# RF.net
KiCad netlist of a schematic drawn in Altium Designer
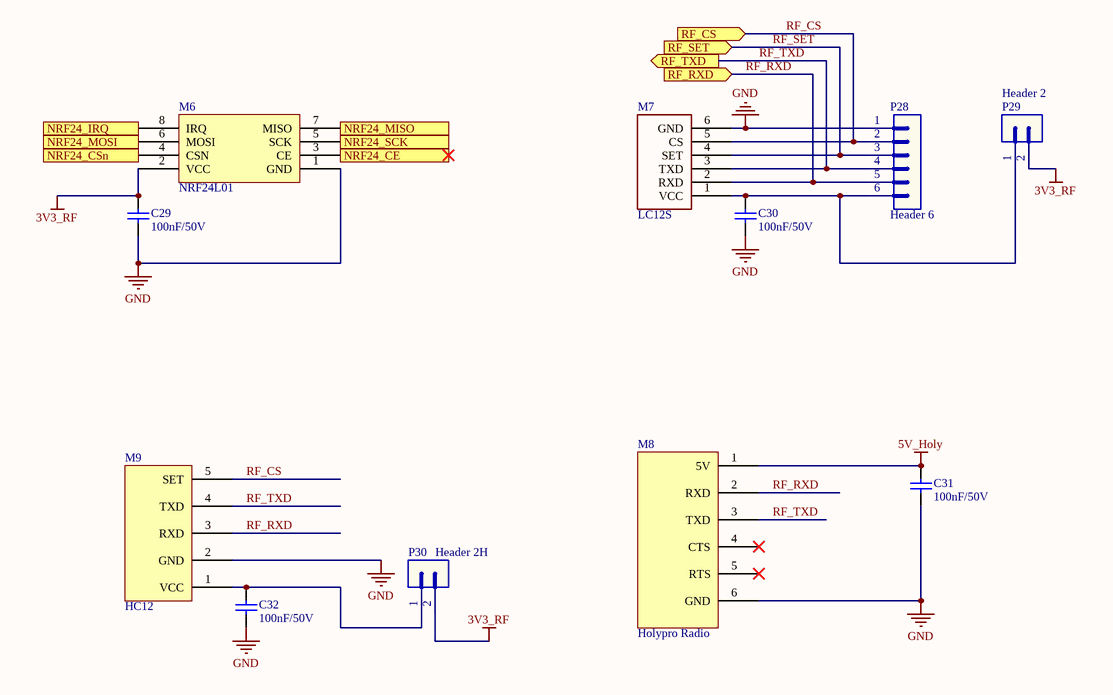
[diagram p0: RF.schdoc]

(export (version "E")
  (design (tool "Eeschema 10.0.6"))
  (components
    (comp (ref "C29")
      (value "100nF/50V")
      (footprint "CAP-SM-0805")
      (description "CAP CER 0.1UF 50V Y5V 0805")
      (fields
        (field (name "MANUFACTURER") "Samsung Electro-Mechanics")
        (field (name "MANUFACTURER PART NUMBER") "CL21F104ZBCNNNC")
      )
      (libsource (lib "Capacitor") (part "Cap-100nF-50V-0805"))
    )
    (comp (ref "C30")
      (value "100nF/50V")
      (footprint "CAP-SM-0805")
      (description "CAP CER 0.1UF 50V Y5V 0805")
      (fields
        (field (name "MANUFACTURER") "Samsung Electro-Mechanics")
        (field (name "MANUFACTURER PART NUMBER") "CL21F104ZBCNNNC")
      )
      (libsource (lib "Capacitor") (part "Cap-100nF-50V-0805"))
    )
    (comp (ref "C31")
      (value "100nF/50V")
      (footprint "CAP-SM-0805")
      (description "CAP CER 0.1UF 50V Y5V 0805")
      (fields
        (field (name "MANUFACTURER") "Samsung Electro-Mechanics")
        (field (name "MANUFACTURER PART NUMBER") "CL21F104ZBCNNNC")
      )
      (libsource (lib "Capacitor") (part "Cap-100nF-50V-0805"))
    )
    (comp (ref "C32")
      (value "100nF/50V")
      (footprint "CAP-SM-0805")
      (description "CAP CER 0.1UF 50V Y5V 0805")
      (fields
        (field (name "MANUFACTURER") "Samsung Electro-Mechanics")
        (field (name "MANUFACTURER PART NUMBER") "CL21F104ZBCNNNC")
      )
      (libsource (lib "Capacitor") (part "Cap-100nF-50V-0805"))
    )
    (comp (ref "M6") (value "NRF24L01") (footprint "NRF24L01") (libsource (lib "Bai1 (1)") (part "NRF24L01")))
    (comp (ref "M7") (value "LC12S") (footprint "LC12S") (libsource (lib "Board") (part "LC12S")))
    (comp (ref "M8")
      (value "Holypro Radio")
      (footprint "holybro:PCBComponent_1")
      (libsource (lib "Bai1 (1)") (part "Holypro Radio"))
    )
    (comp (ref "M9")
      (value "HC12")
      (footprint "hc12 (1):PCBComponent_1")
      (fields (field (name "LOCAL SUPPLIER PART NUMBER") "HS000897"))
      (libsource (lib "Bai1 (1)") (part "HC12"))
    )
    (comp (ref "P28")
      (value "Header 6")
      (footprint "JP6")
      (description "Header, 6-Pin")
      (fields (field (name "PUBLISHER") "Altium Limited"))
      (libsource (lib "Header-connector") (part "Header 6"))
    )
    (comp (ref "P29")
      (value "Header 2")
      (footprint "JP2")
      (description "Header, 2-Pin")
      (fields (field (name "PUBLISHER") "Altium Limited"))
      (libsource (lib "Header-connector") (part "Header 2"))
    )
    (comp (ref "P30")
      (value "Header 2H")
      (footprint "JP2H")
      (description "Header, 2-Pin, Right Angle")
      (fields (field (name "PUBLISHER") "Altium Limited"))
      (libsource (lib "Header-connector") (part "Header 2H"))
    )
  )
  (nets
    (net (code "1") (name "/NRF24_CE") (class "Default")
      (node (ref "M6") (pin "3") (pinfunction "CE_3") (pintype "passive"))
    )
    (net (code "2") (name "/NRF24_CSn") (class "Default")
      (node (ref "M6") (pin "4") (pinfunction "CSN_4") (pintype "passive"))
    )
    (net (code "3") (name "/NRF24_IRQ") (class "Default")
      (node (ref "M6") (pin "8") (pinfunction "IRQ_8") (pintype "passive"))
    )
    (net (code "4") (name "/NRF24_MISO") (class "Default")
      (node (ref "M6") (pin "7") (pinfunction "MISO_7") (pintype "passive"))
    )
    (net (code "5") (name "/NRF24_MOSI") (class "Default")
      (node (ref "M6") (pin "6") (pinfunction "MOSI_6") (pintype "passive"))
    )
    (net (code "6") (name "/NRF24_SCK") (class "Default")
      (node (ref "M6") (pin "5") (pinfunction "SCK_5") (pintype "passive"))
    )
    (net (code "7") (name "/RF_CS") (class "Default")
      (node (ref "M7") (pin "5") (pinfunction "CS_5") (pintype "passive"))
      (node (ref "M9") (pin "5") (pinfunction "SET_5") (pintype "passive"))
      (node (ref "P28") (pin "2") (pinfunction "2_2") (pintype "passive"))
    )
    (net (code "8") (name "/RF_RXD") (class "Default")
      (node (ref "M7") (pin "2") (pinfunction "RXD_2") (pintype "passive"))
      (node (ref "M8") (pin "2") (pinfunction "RXD_2") (pintype "passive"))
      (node (ref "M9") (pin "3") (pinfunction "RXD_3") (pintype "passive"))
      (node (ref "P28") (pin "5") (pinfunction "5_5") (pintype "passive"))
    )
    (net (code "9") (name "/RF_SET") (class "Default")
      (node (ref "M7") (pin "4") (pinfunction "SET_4") (pintype "passive"))
      (node (ref "P28") (pin "3") (pinfunction "3_3") (pintype "passive"))
    )
    (net (code "10") (name "/RF_TXD") (class "Default")
      (node (ref "M7") (pin "3") (pinfunction "TXD_3") (pintype "passive"))
      (node (ref "M8") (pin "3") (pinfunction "TXD_3") (pintype "passive"))
      (node (ref "M9") (pin "4") (pinfunction "TXD_4") (pintype "passive"))
      (node (ref "P28") (pin "4") (pinfunction "4_4") (pintype "passive"))
    )
    (net (code "11") (name "3V3_RF") (class "Default")
      (node (ref "C29") (pin "2") (pinfunction "2_2") (pintype "passive"))
      (node (ref "M6") (pin "2") (pinfunction "VCC_2") (pintype "passive"))
      (node (ref "P29") (pin "2") (pinfunction "2_2") (pintype "passive"))
      (node (ref "P30") (pin "2") (pinfunction "2_2") (pintype "passive"))
    )
    (net (code "12") (name "5V_Holy") (class "Default")
      (node (ref "C31") (pin "2") (pinfunction "2_2") (pintype "passive"))
      (node (ref "M8") (pin "1") (pinfunction "5V_1") (pintype "passive"))
    )
    (net (code "13") (name "GND") (class "Default")
      (node (ref "C29") (pin "1") (pinfunction "1_1") (pintype "passive"))
      (node (ref "C30") (pin "1") (pinfunction "1_1") (pintype "passive"))
      (node (ref "C31") (pin "1") (pinfunction "1_1") (pintype "passive"))
      (node (ref "C32") (pin "1") (pinfunction "1_1") (pintype "passive"))
      (node (ref "M6") (pin "1") (pinfunction "GND_1") (pintype "passive"))
      (node (ref "M7") (pin "6") (pinfunction "GND_6") (pintype "passive"))
      (node (ref "M8") (pin "6") (pinfunction "GND_6") (pintype "passive"))
      (node (ref "M9") (pin "2") (pinfunction "GND_2") (pintype "passive"))
      (node (ref "P28") (pin "1") (pinfunction "1_1") (pintype "passive"))
    )
    (net (code "14") (name "Net-(M7-VCC)") (class "Default")
      (node (ref "C30") (pin "2") (pinfunction "2_2") (pintype "passive"))
      (node (ref "M7") (pin "1") (pinfunction "VCC_1") (pintype "passive"))
      (node (ref "P28") (pin "6") (pinfunction "6_6") (pintype "passive"))
      (node (ref "P29") (pin "1") (pinfunction "1_1") (pintype "passive"))
    )
    (net (code "15") (name "Net-(M9-VCC)") (class "Default")
      (node (ref "C32") (pin "2") (pinfunction "2_2") (pintype "passive"))
      (node (ref "M9") (pin "1") (pinfunction "VCC_1") (pintype "passive"))
      (node (ref "P30") (pin "1") (pinfunction "1_1") (pintype "passive"))
    )
    (net (code "16") (name "unconnected-(M8-CTS-Pad4)") (class "Default")
      (node (ref "M8") (pin "4") (pinfunction "CTS_4") (pintype "passive+no_connect"))
    )
    (net (code "17") (name "unconnected-(M8-RTS-Pad5)") (class "Default")
      (node (ref "M8") (pin "5") (pinfunction "RTS_5") (pintype "passive+no_connect"))
    )
  )
)
